# schCambiennhietdotestboard.net
KiCad netlist of a schematic drawn in Altium Designer
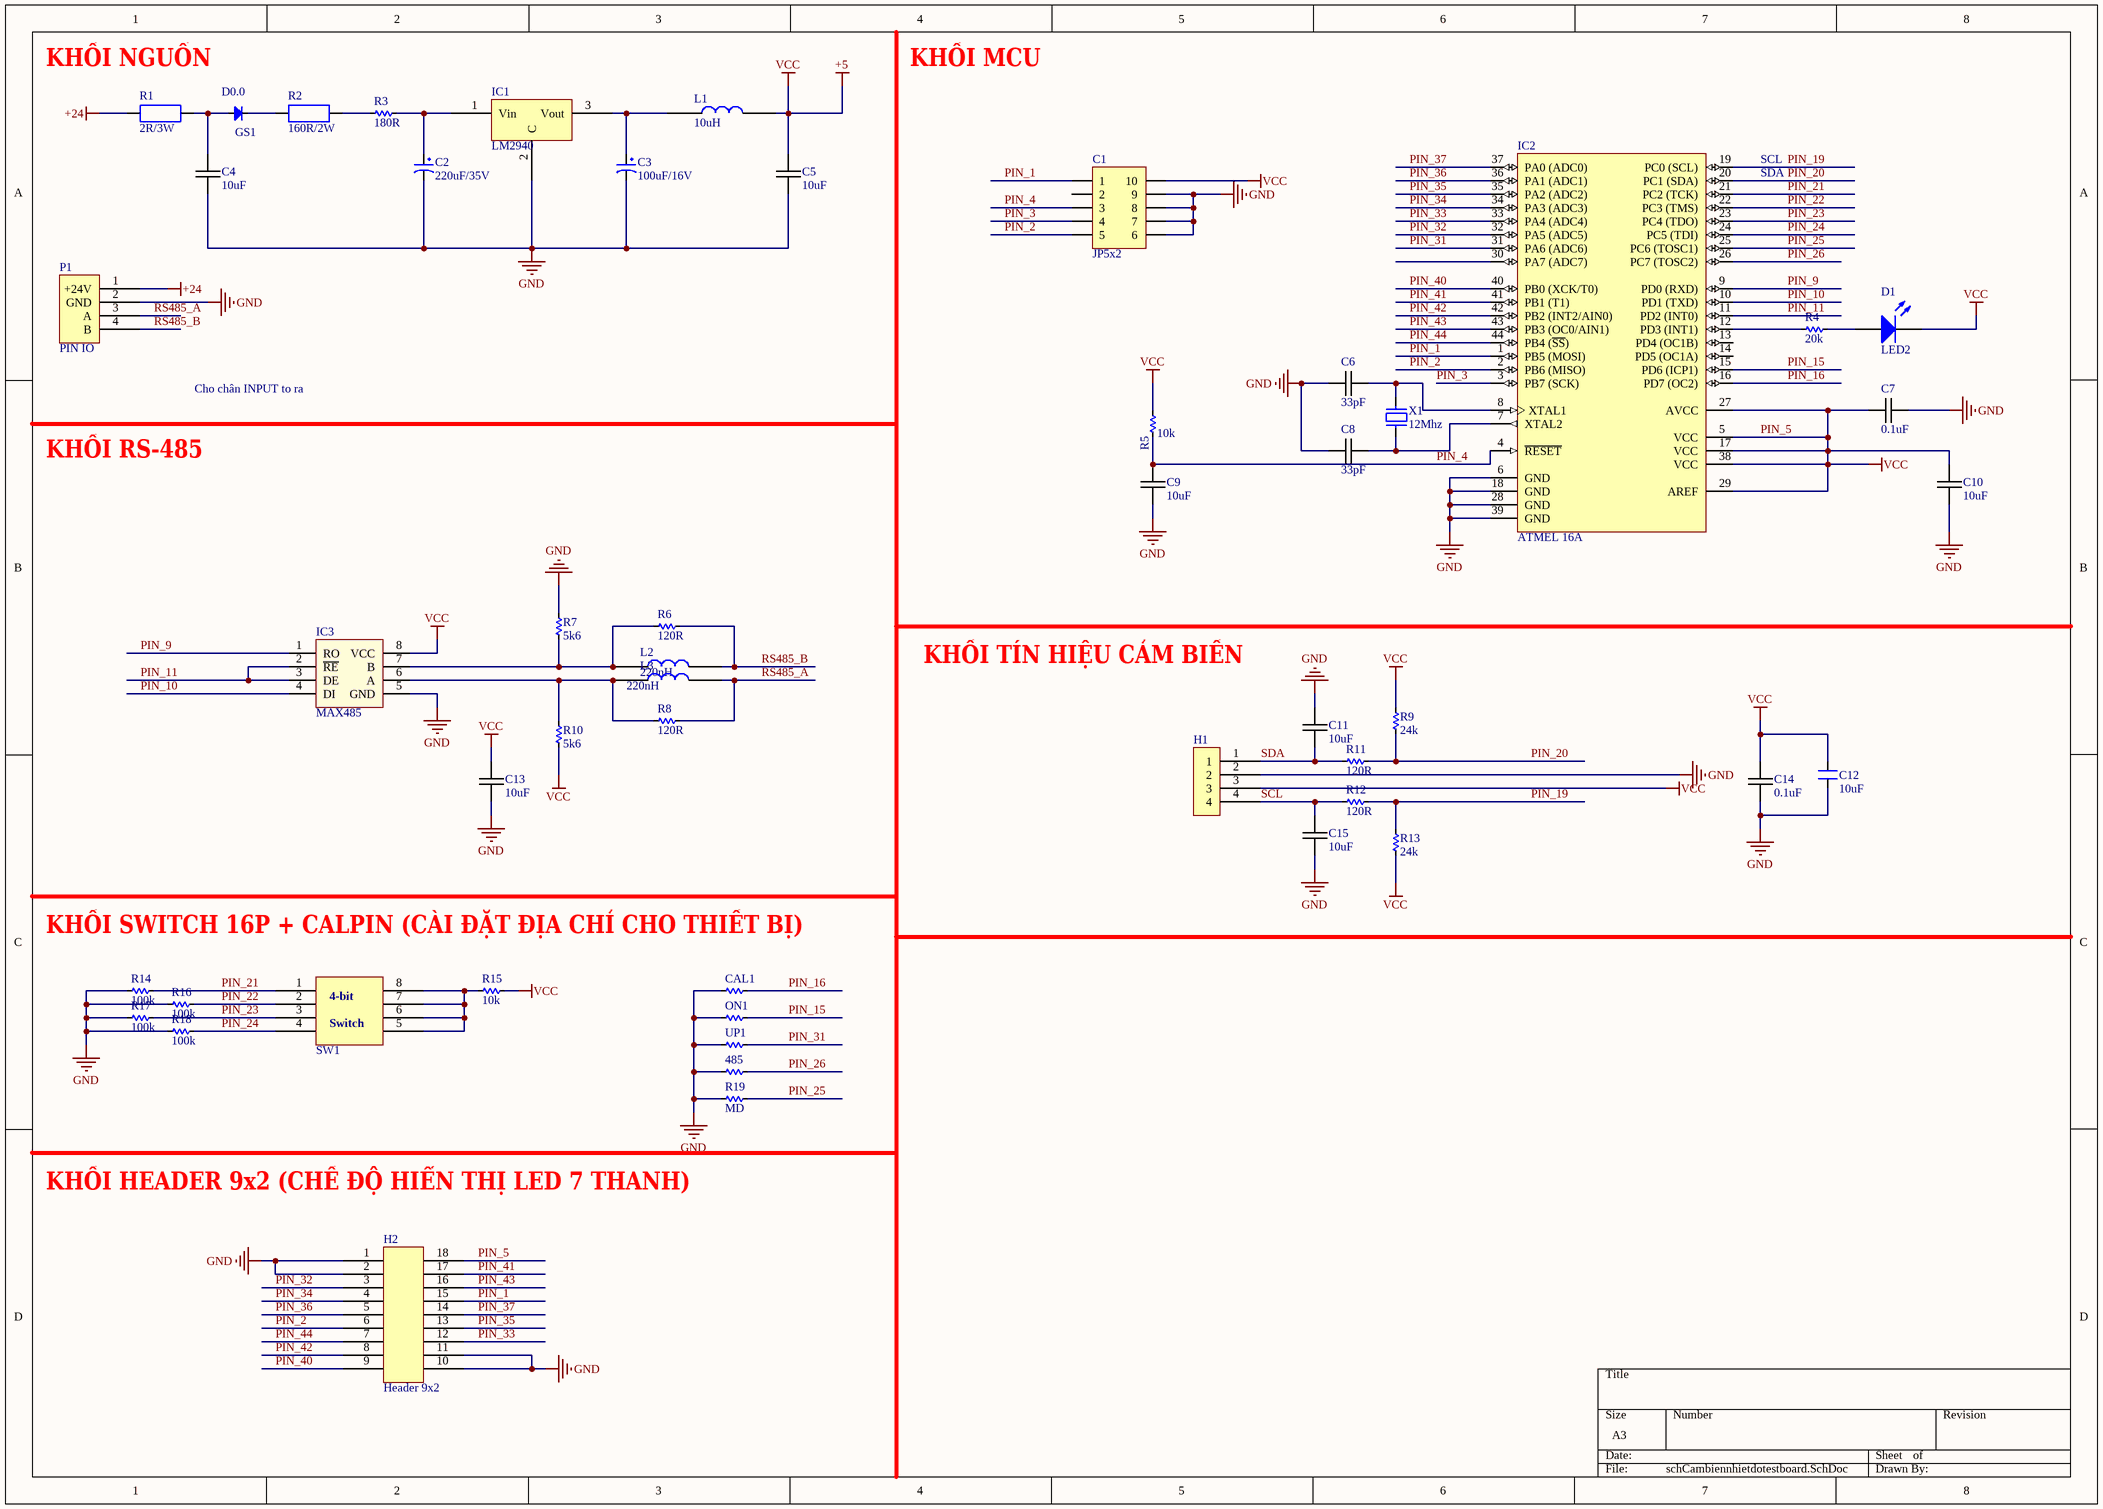
[diagram p0: schCambiennhietdotestboard.SchDoc]

(export (version "E")
  (design (tool "Eeschema 10.0.6"))
  (components
    (comp (ref "485")
      (value "0R")
      (footprint "RES-SMD-0805")
      (description "Resistor")
      (fields
        (field (name "MANUFACTURER") "Generic Components")
        (field (name "PUBLISHER") "Altium Hobart Technology Centre")
      )
      (libsource (lib "LIBRARY") (part "Res-SMD"))
    )
    (comp (ref "C1")
      (value "JP5x2")
      (footprint "JP5-D2T")
      (description "WR-PHD 2.54 mm Dual Socket Header")
      (fields
        (field (name "MANUFACTURER") "Würth Elektronik eiSos GmbH")
        (field (name "PARTNO") "61301021821")
        (field (name "CREATED BY") "Karrer Zheng")
      )
      (libsource (lib "LIBRARY") (part "JP5x2"))
    )
    (comp (ref "C2")
      (value "220uF/35V")
      (footprint "CP1.5/3.4")
      (description "Cap 100uF/35V - 470uF/16V")
      (libsource (lib "syhaunguyen") (part "CP3"))
    )
    (comp (ref "C3")
      (value "100uF/16V")
      (footprint "CP1/2")
      (description "Cap P  0,1uF < 22uF , 16 - 50V")
      (libsource (lib "syhaunguyen") (part "CP1"))
    )
    (comp (ref "C4")
      (value "10uF")
      (footprint "1206C-GENERIC")
      (description "GENERIC CAPACITOR NON POLARISED 1206")
      (fields
        (field (name "MANUFACTURER PART NUMBER") "GMK316F106ZL-T")
        (field (name "MANUFACTURER") "Taiyo Yuden")
      )
      (libsource (lib "vh_altium_library") (part "1206C-10U-35V-X7R"))
    )
    (comp (ref "C5")
      (value "10uF")
      (footprint "0805C-GENERIC")
      (description "CAPACITOR 0805 CERAMIC")
      (libsource (lib "vh_altium_library") (part "0805C-10UF-25V-X5R-SAM"))
    )
    (comp (ref "C6")
      (value "33pF")
      (footprint "CN-SMD-0805")
      (description "GENERIC CAPACITOR NON POLARISED 1206")
      (fields
        (field (name "MANUFACTURER PART NUMBER") "GMK316F106ZL-T")
        (field (name "MANUFACTURER") "Taiyo Yuden")
      )
      (libsource (lib "vh_altium_library") (part "1206C-10U-35V-X7R"))
    )
    (comp (ref "C7")
      (value "0.1uF")
      (footprint "CN-SMD-0805")
      (description "GENERIC CAPACITOR NON POLARISED 1206")
      (fields
        (field (name "MANUFACTURER PART NUMBER") "GMK316F106ZL-T")
        (field (name "MANUFACTURER") "Taiyo Yuden")
      )
      (libsource (lib "vh_altium_library") (part "1206C-10U-35V-X7R"))
    )
    (comp (ref "C8")
      (value "33pF")
      (footprint "CN-SMD-0805")
      (description "GENERIC CAPACITOR NON POLARISED 1206")
      (fields
        (field (name "MANUFACTURER PART NUMBER") "GMK316F106ZL-T")
        (field (name "MANUFACTURER") "Taiyo Yuden")
      )
      (libsource (lib "vh_altium_library") (part "1206C-10U-35V-X7R"))
    )
    (comp (ref "C9")
      (value "10uF")
      (footprint "CN-SMD-0805")
      (description "GENERIC CAPACITOR NON POLARISED 1206")
      (fields
        (field (name "MANUFACTURER PART NUMBER") "GMK316F106ZL-T")
        (field (name "MANUFACTURER") "Taiyo Yuden")
      )
      (libsource (lib "vh_altium_library") (part "1206C-10U-35V-X7R"))
    )
    (comp (ref "C10")
      (value "10uF")
      (footprint "CN-SMD-0805")
      (description "GENERIC CAPACITOR NON POLARISED 1206")
      (fields
        (field (name "MANUFACTURER PART NUMBER") "GMK316F106ZL-T")
        (field (name "MANUFACTURER") "Taiyo Yuden")
      )
      (libsource (lib "vh_altium_library") (part "1206C-10U-35V-X7R"))
    )
    (comp (ref "C11")
      (value "10uF")
      (footprint "CN-SMD-0805")
      (description "GENERIC CAPACITOR NON POLARISED 1206")
      (fields
        (field (name "MANUFACTURER PART NUMBER") "GMK316F106ZL-T")
        (field (name "MANUFACTURER") "Taiyo Yuden")
      )
      (libsource (lib "vh_altium_library") (part "1206C-10U-35V-X7R"))
    )
    (comp (ref "C12")
      (value "10uF")
      (footprint "SM-1206")
      (description "Cap SMD")
      (libsource (lib "Cty1") (part "CM"))
    )
    (comp (ref "C13")
      (value "10uF")
      (footprint "CN-SMD-0805")
      (description "GENERIC CAPACITOR NON POLARISED 1206")
      (fields
        (field (name "MANUFACTURER PART NUMBER") "GMK316F106ZL-T")
        (field (name "MANUFACTURER") "Taiyo Yuden")
      )
      (libsource (lib "vh_altium_library") (part "1206C-10U-35V-X7R"))
    )
    (comp (ref "C14")
      (value "0.1uF")
      (footprint "CN-SMD-0805")
      (description "GENERIC CAPACITOR NON POLARISED 1206")
      (fields
        (field (name "MANUFACTURER PART NUMBER") "GMK316F106ZL-T")
        (field (name "MANUFACTURER") "Taiyo Yuden")
      )
      (libsource (lib "vh_altium_library") (part "1206C-10U-35V-X7R"))
    )
    (comp (ref "C15")
      (value "10uF")
      (footprint "CN-SMD-0805")
      (description "GENERIC CAPACITOR NON POLARISED 1206")
      (fields
        (field (name "MANUFACTURER PART NUMBER") "GMK316F106ZL-T")
        (field (name "MANUFACTURER") "Taiyo Yuden")
      )
      (libsource (lib "vh_altium_library") (part "1206C-10U-35V-X7R"))
    )
    (comp (ref "CAL1")
      (value "0R")
      (footprint "RES-SMD-0805")
      (description "Resistor")
      (fields
        (field (name "MANUFACTURER") "Generic Components")
        (field (name "PUBLISHER") "Altium Hobart Technology Centre")
      )
      (libsource (lib "LIBRARY") (part "Res-SMD"))
    )
    (comp (ref "D1")
      (value "LED2")
      (footprint "LED-0805-Red")
      (description "Typical RED, GREEN, YELLOW, AMBER GaAs LED")
      (fields (field (name "PUBLISHER") "Altium Limited"))
      (libsource (lib "Miscellaneous Devices") (part "LED2"))
    )
    (comp (ref "GS1")
      (value "D0.0")
      (footprint "DIO-SMD-106")
      (description "Default Diode")
      (fields (field (name "PUBLISHER") "Altium Limited"))
      (libsource (lib "LIBRARY") (part "Diode SMD"))
    )
    (comp (ref "H1")
      (value "Header4P")
      (footprint "HEADER4P")
      (libsource (lib "schLibHeader4P") (part "HEADER4_PIN"))
    )
    (comp (ref "H2")
      (value "Header 9x2")
      (footprint "HEADER9x2-2.54mm")
      (description "Header 9x2 2.54mm")
      (libsource (lib "schLibHeader9x2") (part "HEADER9x2"))
    )
    (comp (ref "IC1") (value "LM2940") (footprint "QTO-220") (libsource (lib "schLibTL-780") (part "TL-780")))
    (comp (ref "IC2")
      (value "ATMEL 16A")
      (footprint "TQFP44")
      (libsource (lib "LIBRARY") (part "ATmega16A-AU"))
    )
    (comp (ref "IC3")
      (value "MAX485")
      (footprint "SO8")
      (description "RS232 - RS485 (Same sn75176)")
      (libsource (lib "LIBRARY") (part "MAX485"))
    )
    (comp (ref "L1") (value "10uH") (footprint "RES-1WD") (libsource (lib "Inductor1210") (part "L")))
    (comp (ref "L2") (value "220nH") (footprint "RES-SMD-0805") (libsource (lib "Inductor1210") (part "L")))
    (comp (ref "L3") (value "220nH") (footprint "RES-SMD-0805") (libsource (lib "Inductor1210") (part "L")))
    (comp (ref "ON1")
      (value "0R")
      (footprint "RES-SMD-0805")
      (description "Resistor")
      (fields
        (field (name "MANUFACTURER") "Generic Components")
        (field (name "PUBLISHER") "Altium Hobart Technology Centre")
      )
      (libsource (lib "LIBRARY") (part "Res-SMD"))
    )
    (comp (ref "P1")
      (value "PIN IO")
      (footprint "pcbLibPIN1")
      (description "Input source 24V and RS485pin")
      (libsource (lib "schLibPin1") (part "PIN"))
    )
    (comp (ref "R1")
      (value "2R/3W")
      (footprint "R2WD")
      (description "Resistor 2W")
      (libsource (lib "syhaunguyen") (part "R2W"))
    )
    (comp (ref "R2")
      (value "160R/2W")
      (footprint "R2WD")
      (description "Resistor 2W")
      (libsource (lib "syhaunguyen") (part "R2W"))
    )
    (comp (ref "R3")
      (value "180R")
      (footprint "RES-SMD-2512")
      (description "Resistor")
      (fields
        (field (name "MANUFACTURER") "Generic Components")
        (field (name "PUBLISHER") "Altium Hobart Technology Centre")
      )
      (libsource (lib "LIBRARY") (part "Res-SMD"))
    )
    (comp (ref "R4")
      (value "20k")
      (footprint "RES-SMD-0805")
      (description "Resistor")
      (fields
        (field (name "MANUFACTURER") "Generic Components")
        (field (name "PUBLISHER") "Altium Hobart Technology Centre")
      )
      (libsource (lib "LIBRARY") (part "Res-SMD"))
    )
    (comp (ref "R5")
      (value "10k")
      (footprint "RES-SMD-0805")
      (description "Resistor")
      (fields
        (field (name "MANUFACTURER") "Generic Components")
        (field (name "PUBLISHER") "Altium Hobart Technology Centre")
      )
      (libsource (lib "LIBRARY") (part "Res-SMD"))
    )
    (comp (ref "R6")
      (value "120R")
      (footprint "RES-SMD-0805")
      (description "Resistor")
      (fields
        (field (name "MANUFACTURER") "Generic Components")
        (field (name "PUBLISHER") "Altium Hobart Technology Centre")
      )
      (libsource (lib "LIBRARY") (part "Res-SMD"))
    )
    (comp (ref "R7")
      (value "5k6")
      (footprint "RES-SMD-0805")
      (description "Resistor")
      (fields
        (field (name "MANUFACTURER") "Generic Components")
        (field (name "PUBLISHER") "Altium Hobart Technology Centre")
      )
      (libsource (lib "LIBRARY") (part "Res-SMD"))
    )
    (comp (ref "R8")
      (value "120R")
      (footprint "RES-SMD-0805")
      (description "Resistor")
      (fields
        (field (name "MANUFACTURER") "Generic Components")
        (field (name "PUBLISHER") "Altium Hobart Technology Centre")
      )
      (libsource (lib "LIBRARY") (part "Res-SMD"))
    )
    (comp (ref "R9")
      (value "24k")
      (footprint "RES-SMD-0805")
      (description "Resistor")
      (fields
        (field (name "MANUFACTURER") "Generic Components")
        (field (name "PUBLISHER") "Altium Hobart Technology Centre")
      )
      (libsource (lib "LIBRARY") (part "Res-SMD"))
    )
    (comp (ref "R10")
      (value "5k6")
      (footprint "RES-SMD-0805")
      (description "Resistor")
      (fields
        (field (name "MANUFACTURER") "Generic Components")
        (field (name "PUBLISHER") "Altium Hobart Technology Centre")
      )
      (libsource (lib "LIBRARY") (part "Res-SMD"))
    )
    (comp (ref "R11")
      (value "120R")
      (footprint "RES-SMD-0805")
      (description "Resistor")
      (fields
        (field (name "MANUFACTURER") "Generic Components")
        (field (name "PUBLISHER") "Altium Hobart Technology Centre")
      )
      (libsource (lib "LIBRARY") (part "Res-SMD"))
    )
    (comp (ref "R12")
      (value "120R")
      (footprint "RES-SMD-0805")
      (description "Resistor")
      (fields
        (field (name "MANUFACTURER") "Generic Components")
        (field (name "PUBLISHER") "Altium Hobart Technology Centre")
      )
      (libsource (lib "LIBRARY") (part "Res-SMD"))
    )
    (comp (ref "R13")
      (value "24k")
      (footprint "RES-SMD-0805")
      (description "Resistor")
      (fields
        (field (name "MANUFACTURER") "Generic Components")
        (field (name "PUBLISHER") "Altium Hobart Technology Centre")
      )
      (libsource (lib "LIBRARY") (part "Res-SMD"))
    )
    (comp (ref "R14")
      (value "100k")
      (footprint "RES-SMD-0805")
      (description "Resistor")
      (fields
        (field (name "MANUFACTURER") "Generic Components")
        (field (name "PUBLISHER") "Altium Hobart Technology Centre")
      )
      (libsource (lib "LIBRARY") (part "Res-SMD"))
    )
    (comp (ref "R15")
      (value "10k")
      (footprint "RES-SMD-0805")
      (description "Resistor")
      (fields
        (field (name "MANUFACTURER") "Generic Components")
        (field (name "PUBLISHER") "Altium Hobart Technology Centre")
      )
      (libsource (lib "LIBRARY") (part "Res-SMD"))
    )
    (comp (ref "R16")
      (value "100k")
      (footprint "RES-SMD-0805")
      (description "Resistor")
      (fields
        (field (name "MANUFACTURER") "Generic Components")
        (field (name "PUBLISHER") "Altium Hobart Technology Centre")
      )
      (libsource (lib "LIBRARY") (part "Res-SMD"))
    )
    (comp (ref "R17")
      (value "100k")
      (footprint "RES-SMD-0805")
      (description "Resistor")
      (fields
        (field (name "MANUFACTURER") "Generic Components")
        (field (name "PUBLISHER") "Altium Hobart Technology Centre")
      )
      (libsource (lib "LIBRARY") (part "Res-SMD"))
    )
    (comp (ref "R18")
      (value "100k")
      (footprint "RES-SMD-0805")
      (description "Resistor")
      (fields
        (field (name "MANUFACTURER") "Generic Components")
        (field (name "PUBLISHER") "Altium Hobart Technology Centre")
      )
      (libsource (lib "LIBRARY") (part "Res-SMD"))
    )
    (comp (ref "R19")
      (value "MD")
      (footprint "RES-SMD-0805")
      (description "Resistor")
      (fields
        (field (name "MANUFACTURER") "Generic Components")
        (field (name "PUBLISHER") "Altium Hobart Technology Centre")
      )
      (libsource (lib "LIBRARY") (part "Res-SMD"))
    )
    (comp (ref "SW1")
      (value "Switch 4bit")
      (footprint "SW-4-BIT-SMD")
      (libsource (lib "Congtac4Bit") (part "Switch  4 bit"))
    )
    (comp (ref "UP1")
      (value "0R")
      (footprint "RES-SMD-0805")
      (description "Resistor")
      (fields
        (field (name "MANUFACTURER") "Generic Components")
        (field (name "PUBLISHER") "Altium Hobart Technology Centre")
      )
      (libsource (lib "LIBRARY") (part "Res-SMD"))
    )
    (comp (ref "X1")
      (value "12Mhz")
      (footprint "XTAL-RU49/4")
      (description "Crystal, 32.768 KHz, -40 to 85 degC, 3.2 x 1.5 x 0.9 mm SMD")
      (libsource (lib "LIBRARY") (part "XT2"))
    )
  )
  (nets
    (net (code "1") (name "+5") (class "Default")
      (node (ref "C1") (pin "10") (pinfunction "10_10") (pintype "passive"))
      (node (ref "C10") (pin "1") (pintype "passive"))
      (node (ref "C12") (pin "2") (pinfunction "2_2") (pintype "passive"))
      (node (ref "C13") (pin "1") (pintype "passive"))
      (node (ref "C14") (pin "1") (pintype "passive"))
      (node (ref "C5") (pin "1") (pintype "passive"))
      (node (ref "C7") (pin "1") (pintype "passive"))
      (node (ref "D1") (pin "2") (pinfunction "K_2") (pintype "passive"))
      (node (ref "H1") (pin "3") (pinfunction "3_3") (pintype "passive"))
      (node (ref "H2") (pin "18") (pinfunction "18_18") (pintype "passive"))
      (node (ref "IC2") (pin "17") (pinfunction "VCC_17") (pintype "power_in"))
      (node (ref "IC2") (pin "27") (pinfunction "AVCC_27") (pintype "power_in"))
      (node (ref "IC2") (pin "29") (pinfunction "AREF_29") (pintype "power_in"))
      (node (ref "IC2") (pin "38") (pinfunction "VCC_38") (pintype "power_in"))
      (node (ref "IC2") (pin "5") (pinfunction "VCC_5") (pintype "power_in"))
      (node (ref "IC3") (pin "8") (pinfunction "VCC_8") (pintype "passive"))
      (node (ref "L1") (pin "2") (pinfunction "2_2") (pintype "passive"))
      (node (ref "R10") (pin "2") (pinfunction "2_2") (pintype "passive"))
      (node (ref "R13") (pin "1") (pinfunction "1_1") (pintype "passive"))
      (node (ref "R15") (pin "1") (pinfunction "1_1") (pintype "passive"))
      (node (ref "R5") (pin "1") (pinfunction "1_1") (pintype "passive"))
      (node (ref "R9") (pin "1") (pinfunction "1_1") (pintype "passive"))
    )
    (net (code "2") (name "+24") (class "Default")
      (node (ref "P1") (pin "1") (pinfunction "+24V_1") (pintype "passive"))
      (node (ref "R1") (pin "2") (pinfunction "2_2") (pintype "passive"))
    )
    (net (code "3") (name "/PIN_1") (class "Default")
      (node (ref "C1") (pin "1") (pinfunction "1_1") (pintype "passive"))
      (node (ref "H2") (pin "15") (pinfunction "15_15") (pintype "passive"))
      (node (ref "IC2") (pin "1") (pinfunction "PB5_(MOSI)_1") (pintype "bidirectional"))
    )
    (net (code "4") (name "/PIN_2") (class "Default")
      (node (ref "C1") (pin "5") (pinfunction "5_5") (pintype "passive"))
      (node (ref "H2") (pin "6") (pinfunction "6_6") (pintype "passive"))
      (node (ref "IC2") (pin "2") (pinfunction "PB6_(MISO)_2") (pintype "bidirectional"))
    )
    (net (code "5") (name "/PIN_3") (class "Default")
      (node (ref "C1") (pin "4") (pinfunction "4_4") (pintype "passive"))
      (node (ref "IC2") (pin "3") (pinfunction "PB7_(SCK)_3") (pintype "bidirectional"))
    )
    (net (code "6") (name "/PIN_4") (class "Default")
      (node (ref "C1") (pin "3") (pinfunction "3_3") (pintype "passive"))
      (node (ref "C9") (pin "1") (pintype "passive"))
      (node (ref "IC2") (pin "4") (pinfunction "~{RESET}_4") (pintype "input"))
      (node (ref "R5") (pin "2") (pinfunction "2_2") (pintype "passive"))
    )
    (net (code "7") (name "/PIN_9") (class "Default")
      (node (ref "IC2") (pin "9") (pinfunction "PD0_(RXD)_9") (pintype "bidirectional"))
      (node (ref "IC3") (pin "1") (pinfunction "RO_1") (pintype "passive"))
    )
    (net (code "8") (name "/PIN_10") (class "Default")
      (node (ref "IC2") (pin "10") (pinfunction "PD1_(TXD)_10") (pintype "bidirectional"))
      (node (ref "IC3") (pin "4") (pinfunction "DI_4") (pintype "passive"))
    )
    (net (code "9") (name "/PIN_11") (class "Default")
      (node (ref "IC2") (pin "11") (pinfunction "PD2_(INT0)_11") (pintype "bidirectional"))
      (node (ref "IC3") (pin "2") (pinfunction "~{RE}_2") (pintype "passive"))
      (node (ref "IC3") (pin "3") (pinfunction "DE_3") (pintype "passive"))
    )
    (net (code "10") (name "/PIN_15") (class "Default")
      (node (ref "IC2") (pin "15") (pinfunction "PD6_(ICP1)_15") (pintype "bidirectional"))
      (node (ref "ON1") (pin "1") (pinfunction "1_1") (pintype "passive"))
    )
    (net (code "11") (name "/PIN_16") (class "Default")
      (node (ref "CAL1") (pin "1") (pinfunction "1_1") (pintype "passive"))
      (node (ref "IC2") (pin "16") (pinfunction "PD7_(OC2)_16") (pintype "bidirectional"))
    )
    (net (code "12") (name "/PIN_19") (class "Default")
      (node (ref "IC2") (pin "19") (pinfunction "PC0_(SCL)_19") (pintype "bidirectional"))
      (node (ref "R12") (pin "1") (pinfunction "1_1") (pintype "passive"))
      (node (ref "R13") (pin "2") (pinfunction "2_2") (pintype "passive"))
    )
    (net (code "13") (name "/PIN_20") (class "Default")
      (node (ref "IC2") (pin "20") (pinfunction "PC1_(SDA)_20") (pintype "bidirectional"))
      (node (ref "R11") (pin "2") (pinfunction "2_2") (pintype "passive"))
      (node (ref "R9") (pin "2") (pinfunction "2_2") (pintype "passive"))
    )
    (net (code "14") (name "/PIN_21") (class "Default")
      (node (ref "IC2") (pin "21") (pinfunction "PC2_(TCK)_21") (pintype "bidirectional"))
      (node (ref "R14") (pin "2") (pinfunction "2_2") (pintype "passive"))
      (node (ref "SW1") (pin "1") (pinfunction "1_1") (pintype "passive"))
    )
    (net (code "15") (name "/PIN_22") (class "Default")
      (node (ref "IC2") (pin "22") (pinfunction "PC3_(TMS)_22") (pintype "bidirectional"))
      (node (ref "R16") (pin "2") (pinfunction "2_2") (pintype "passive"))
      (node (ref "SW1") (pin "2") (pinfunction "2_2") (pintype "passive"))
    )
    (net (code "16") (name "/PIN_23") (class "Default")
      (node (ref "IC2") (pin "23") (pinfunction "PC4_(TDO)_23") (pintype "bidirectional"))
      (node (ref "R17") (pin "2") (pinfunction "2_2") (pintype "passive"))
      (node (ref "SW1") (pin "3") (pinfunction "3_3") (pintype "passive"))
    )
    (net (code "17") (name "/PIN_24") (class "Default")
      (node (ref "IC2") (pin "24") (pinfunction "PC5_(TDI)_24") (pintype "bidirectional"))
      (node (ref "R18") (pin "2") (pinfunction "2_2") (pintype "passive"))
      (node (ref "SW1") (pin "4") (pinfunction "4_4") (pintype "passive"))
    )
    (net (code "18") (name "/PIN_25") (class "Default")
      (node (ref "IC2") (pin "25") (pinfunction "PC6_(TOSC1)_25") (pintype "bidirectional"))
      (node (ref "R19") (pin "1") (pinfunction "1_1") (pintype "passive"))
    )
    (net (code "19") (name "/PIN_26") (class "Default")
      (node (ref "485") (pin "1") (pinfunction "1_1") (pintype "passive"))
      (node (ref "IC2") (pin "26") (pinfunction "PC7_(TOSC2)_26") (pintype "bidirectional"))
    )
    (net (code "20") (name "/PIN_31") (class "Default")
      (node (ref "IC2") (pin "31") (pinfunction "PA6_(ADC6)_31") (pintype "bidirectional"))
      (node (ref "UP1") (pin "1") (pinfunction "1_1") (pintype "passive"))
    )
    (net (code "21") (name "/PIN_32") (class "Default")
      (node (ref "H2") (pin "3") (pinfunction "3_3") (pintype "passive"))
      (node (ref "IC2") (pin "32") (pinfunction "PA5_(ADC5)_32") (pintype "bidirectional"))
    )
    (net (code "22") (name "/PIN_33") (class "Default")
      (node (ref "H2") (pin "12") (pinfunction "12_12") (pintype "passive"))
      (node (ref "IC2") (pin "33") (pinfunction "PA4_(ADC4)_33") (pintype "bidirectional"))
    )
    (net (code "23") (name "/PIN_34") (class "Default")
      (node (ref "H2") (pin "4") (pinfunction "4_4") (pintype "passive"))
      (node (ref "IC2") (pin "34") (pinfunction "PA3_(ADC3)_34") (pintype "bidirectional"))
    )
    (net (code "24") (name "/PIN_35") (class "Default")
      (node (ref "H2") (pin "13") (pinfunction "13_13") (pintype "passive"))
      (node (ref "IC2") (pin "35") (pinfunction "PA2_(ADC2)_35") (pintype "bidirectional"))
    )
    (net (code "25") (name "/PIN_36") (class "Default")
      (node (ref "H2") (pin "5") (pinfunction "5_5") (pintype "passive"))
      (node (ref "IC2") (pin "36") (pinfunction "PA1_(ADC1)_36") (pintype "bidirectional"))
    )
    (net (code "26") (name "/PIN_37") (class "Default")
      (node (ref "H2") (pin "14") (pinfunction "14_14") (pintype "passive"))
      (node (ref "IC2") (pin "37") (pinfunction "PA0_(ADC0)_37") (pintype "bidirectional"))
    )
    (net (code "27") (name "/PIN_40") (class "Default")
      (node (ref "H2") (pin "9") (pinfunction "9_9") (pintype "passive"))
      (node (ref "IC2") (pin "40") (pinfunction "PB0_(XCK/T0)_40") (pintype "bidirectional"))
    )
    (net (code "28") (name "/PIN_41") (class "Default")
      (node (ref "H2") (pin "17") (pinfunction "17_17") (pintype "passive"))
      (node (ref "IC2") (pin "41") (pinfunction "PB1_(T1)_41") (pintype "bidirectional"))
    )
    (net (code "29") (name "/PIN_42") (class "Default")
      (node (ref "H2") (pin "8") (pinfunction "8_8") (pintype "passive"))
      (node (ref "IC2") (pin "42") (pinfunction "PB2_(INT2/AIN0)_42") (pintype "bidirectional"))
    )
    (net (code "30") (name "/PIN_43") (class "Default")
      (node (ref "H2") (pin "16") (pinfunction "16_16") (pintype "passive"))
      (node (ref "IC2") (pin "43") (pinfunction "PB3_(OC0/AIN1)_43") (pintype "bidirectional"))
    )
    (net (code "31") (name "/PIN_44") (class "Default")
      (node (ref "H2") (pin "7") (pinfunction "7_7") (pintype "passive"))
      (node (ref "IC2") (pin "44") (pinfunction "PB4_(~{SS})_44") (pintype "bidirectional"))
    )
    (net (code "32") (name "/RS485_A") (class "Default")
      (node (ref "L3") (pin "2") (pinfunction "2_2") (pintype "passive"))
      (node (ref "P1") (pin "3") (pinfunction "A_3") (pintype "passive"))
      (node (ref "R8") (pin "2") (pinfunction "2_2") (pintype "passive"))
    )
    (net (code "33") (name "/RS485_B") (class "Default")
      (node (ref "L2") (pin "2") (pinfunction "2_2") (pintype "passive"))
      (node (ref "P1") (pin "4") (pinfunction "B_4") (pintype "passive"))
      (node (ref "R6") (pin "2") (pinfunction "2_2") (pintype "passive"))
    )
    (net (code "34") (name "/SCL") (class "Default")
      (node (ref "C15") (pin "2") (pintype "passive"))
      (node (ref "H1") (pin "4") (pinfunction "4_4") (pintype "passive"))
      (node (ref "R12") (pin "2") (pinfunction "2_2") (pintype "passive"))
    )
    (net (code "35") (name "/SDA") (class "Default")
      (node (ref "C11") (pin "2") (pintype "passive"))
      (node (ref "H1") (pin "1") (pinfunction "1_1") (pintype "passive"))
      (node (ref "R11") (pin "1") (pinfunction "1_1") (pintype "passive"))
    )
    (net (code "36") (name "GND") (class "Default")
      (node (ref "485") (pin "2") (pinfunction "2_2") (pintype "passive"))
      (node (ref "C1") (pin "6") (pinfunction "6_6") (pintype "passive"))
      (node (ref "C1") (pin "7") (pinfunction "7_7") (pintype "passive"))
      (node (ref "C1") (pin "8") (pinfunction "8_8") (pintype "passive"))
      (node (ref "C1") (pin "9") (pinfunction "9_9") (pintype "passive"))
      (node (ref "C10") (pin "2") (pintype "passive"))
      (node (ref "C11") (pin "1") (pintype "passive"))
      (node (ref "C12") (pin "1") (pinfunction "1_1") (pintype "passive"))
      (node (ref "C13") (pin "2") (pintype "passive"))
      (node (ref "C14") (pin "2") (pintype "passive"))
      (node (ref "C15") (pin "1") (pintype "passive"))
      (node (ref "C2") (pin "2") (pinfunction "2_2") (pintype "passive"))
      (node (ref "C3") (pin "2") (pinfunction "2_2") (pintype "passive"))
      (node (ref "C4") (pin "2") (pintype "passive"))
      (node (ref "C5") (pin "2") (pintype "passive"))
      (node (ref "C6") (pin "1") (pintype "passive"))
      (node (ref "C7") (pin "2") (pintype "passive"))
      (node (ref "C8") (pin "1") (pintype "passive"))
      (node (ref "C9") (pin "2") (pintype "passive"))
      (node (ref "CAL1") (pin "2") (pinfunction "2_2") (pintype "passive"))
      (node (ref "H1") (pin "2") (pinfunction "2_2") (pintype "passive"))
      (node (ref "H2") (pin "1") (pinfunction "1_1") (pintype "passive"))
      (node (ref "H2") (pin "10") (pinfunction "10_10") (pintype "passive"))
      (node (ref "H2") (pin "11") (pinfunction "11_11") (pintype "passive"))
      (node (ref "H2") (pin "2") (pinfunction "2_2") (pintype "passive"))
      (node (ref "IC1") (pin "2") (pinfunction "C_2") (pintype "passive"))
      (node (ref "IC2") (pin "18") (pinfunction "GND_18") (pintype "power_in"))
      (node (ref "IC2") (pin "28") (pinfunction "GND_28") (pintype "power_in"))
      (node (ref "IC2") (pin "39") (pinfunction "GND_39") (pintype "power_in"))
      (node (ref "IC2") (pin "6") (pinfunction "GND_6") (pintype "power_in"))
      (node (ref "IC3") (pin "5") (pinfunction "GND_5") (pintype "passive"))
      (node (ref "ON1") (pin "2") (pinfunction "2_2") (pintype "passive"))
      (node (ref "P1") (pin "2") (pinfunction "GND_2") (pintype "passive"))
      (node (ref "R14") (pin "1") (pinfunction "1_1") (pintype "passive"))
      (node (ref "R16") (pin "1") (pinfunction "1_1") (pintype "passive"))
      (node (ref "R17") (pin "1") (pinfunction "1_1") (pintype "passive"))
      (node (ref "R18") (pin "1") (pinfunction "1_1") (pintype "passive"))
      (node (ref "R19") (pin "2") (pinfunction "2_2") (pintype "passive"))
      (node (ref "R7") (pin "1") (pinfunction "1_1") (pintype "passive"))
      (node (ref "UP1") (pin "2") (pinfunction "2_2") (pintype "passive"))
    )
    (net (code "37") (name "Net-(D1-A)") (class "Default")
      (node (ref "D1") (pin "1") (pinfunction "A_1") (pintype "passive"))
      (node (ref "R4") (pin "2") (pinfunction "2_2") (pintype "passive"))
    )
    (net (code "38") (name "Net-(GS1-A)") (class "Default")
      (node (ref "C4") (pin "1") (pintype "passive"))
      (node (ref "GS1") (pin "1") (pinfunction "A_1") (pintype "passive"))
      (node (ref "R1") (pin "1") (pinfunction "1_1") (pintype "passive"))
    )
    (net (code "39") (name "Net-(GS1-K)") (class "Default")
      (node (ref "GS1") (pin "2") (pinfunction "K_2") (pintype "passive"))
      (node (ref "R2") (pin "2") (pinfunction "2_2") (pintype "passive"))
    )
    (net (code "40") (name "Net-(IC1-Vin)") (class "Default")
      (node (ref "C2") (pin "1") (pinfunction "1_1") (pintype "passive"))
      (node (ref "IC1") (pin "1") (pinfunction "Vin_1") (pintype "passive"))
      (node (ref "R3") (pin "1") (pinfunction "1_1") (pintype "passive"))
    )
    (net (code "41") (name "Net-(IC1-Vout)") (class "Default")
      (node (ref "C3") (pin "1") (pinfunction "1_1") (pintype "passive"))
      (node (ref "IC1") (pin "3") (pinfunction "Vout_3") (pintype "passive"))
      (node (ref "L1") (pin "1") (pinfunction "1_1") (pintype "passive"))
    )
    (net (code "42") (name "Net-(IC2-PD3_(INT1))") (class "Default")
      (node (ref "IC2") (pin "12") (pinfunction "PD3_(INT1)_12") (pintype "bidirectional"))
      (node (ref "R4") (pin "1") (pinfunction "1_1") (pintype "passive"))
    )
    (net (code "43") (name "Net-(IC2-XTAL1)") (class "Default")
      (node (ref "C6") (pin "2") (pintype "passive"))
      (node (ref "IC2") (pin "8") (pinfunction "XTAL1_8") (pintype "input"))
      (node (ref "X1") (pin "2") (pinfunction "2_2") (pintype "passive"))
    )
    (net (code "44") (name "Net-(IC2-XTAL2)") (class "Default")
      (node (ref "C8") (pin "2") (pintype "passive"))
      (node (ref "IC2") (pin "7") (pinfunction "XTAL2_7") (pintype "output"))
      (node (ref "X1") (pin "1") (pinfunction "1_1") (pintype "passive"))
    )
    (net (code "45") (name "Net-(IC3-A)") (class "Default")
      (node (ref "IC3") (pin "6") (pinfunction "A_6") (pintype "passive"))
      (node (ref "L3") (pin "1") (pinfunction "1_1") (pintype "passive"))
      (node (ref "R10") (pin "1") (pinfunction "1_1") (pintype "passive"))
      (node (ref "R8") (pin "1") (pinfunction "1_1") (pintype "passive"))
    )
    (net (code "46") (name "Net-(IC3-B)") (class "Default")
      (node (ref "IC3") (pin "7") (pinfunction "B_7") (pintype "passive"))
      (node (ref "L2") (pin "1") (pinfunction "1_1") (pintype "passive"))
      (node (ref "R6") (pin "1") (pinfunction "1_1") (pintype "passive"))
      (node (ref "R7") (pin "2") (pinfunction "2_2") (pintype "passive"))
    )
    (net (code "47") (name "Net-(R2-Pad1)") (class "Default")
      (node (ref "R2") (pin "1") (pinfunction "1_1") (pintype "passive"))
      (node (ref "R3") (pin "2") (pinfunction "2_2") (pintype "passive"))
    )
    (net (code "48") (name "Net-(R15-Pad2)") (class "Default")
      (node (ref "R15") (pin "2") (pinfunction "2_2") (pintype "passive"))
      (node (ref "SW1") (pin "5") (pinfunction "5_5") (pintype "passive"))
      (node (ref "SW1") (pin "6") (pinfunction "6_6") (pintype "passive"))
      (node (ref "SW1") (pin "7") (pinfunction "7_7") (pintype "passive"))
      (node (ref "SW1") (pin "8") (pinfunction "8_8") (pintype "passive"))
    )
    (net (code "49") (name "unconnected-(C1-Pad2)") (class "Default")
      (node (ref "C1") (pin "2") (pinfunction "2_2") (pintype "passive"))
    )
    (net (code "50") (name "unconnected-(IC2-PA7_(ADC7)-Pad30)") (class "Default")
      (node (ref "IC2") (pin "30") (pinfunction "PA7_(ADC7)_30") (pintype "bidirectional"))
    )
    (net (code "51") (name "unconnected-(IC2-PD4_(OC1B)-Pad13)") (class "Default")
      (node (ref "IC2") (pin "13") (pinfunction "PD4_(OC1B)_13") (pintype "bidirectional"))
    )
    (net (code "52") (name "unconnected-(IC2-PD5_(OC1A)-Pad14)") (class "Default")
      (node (ref "IC2") (pin "14") (pinfunction "PD5_(OC1A)_14") (pintype "bidirectional"))
    )
  )
)
